# 1_V4.net
KiCad netlist of a schematic drawn in Altium Designer
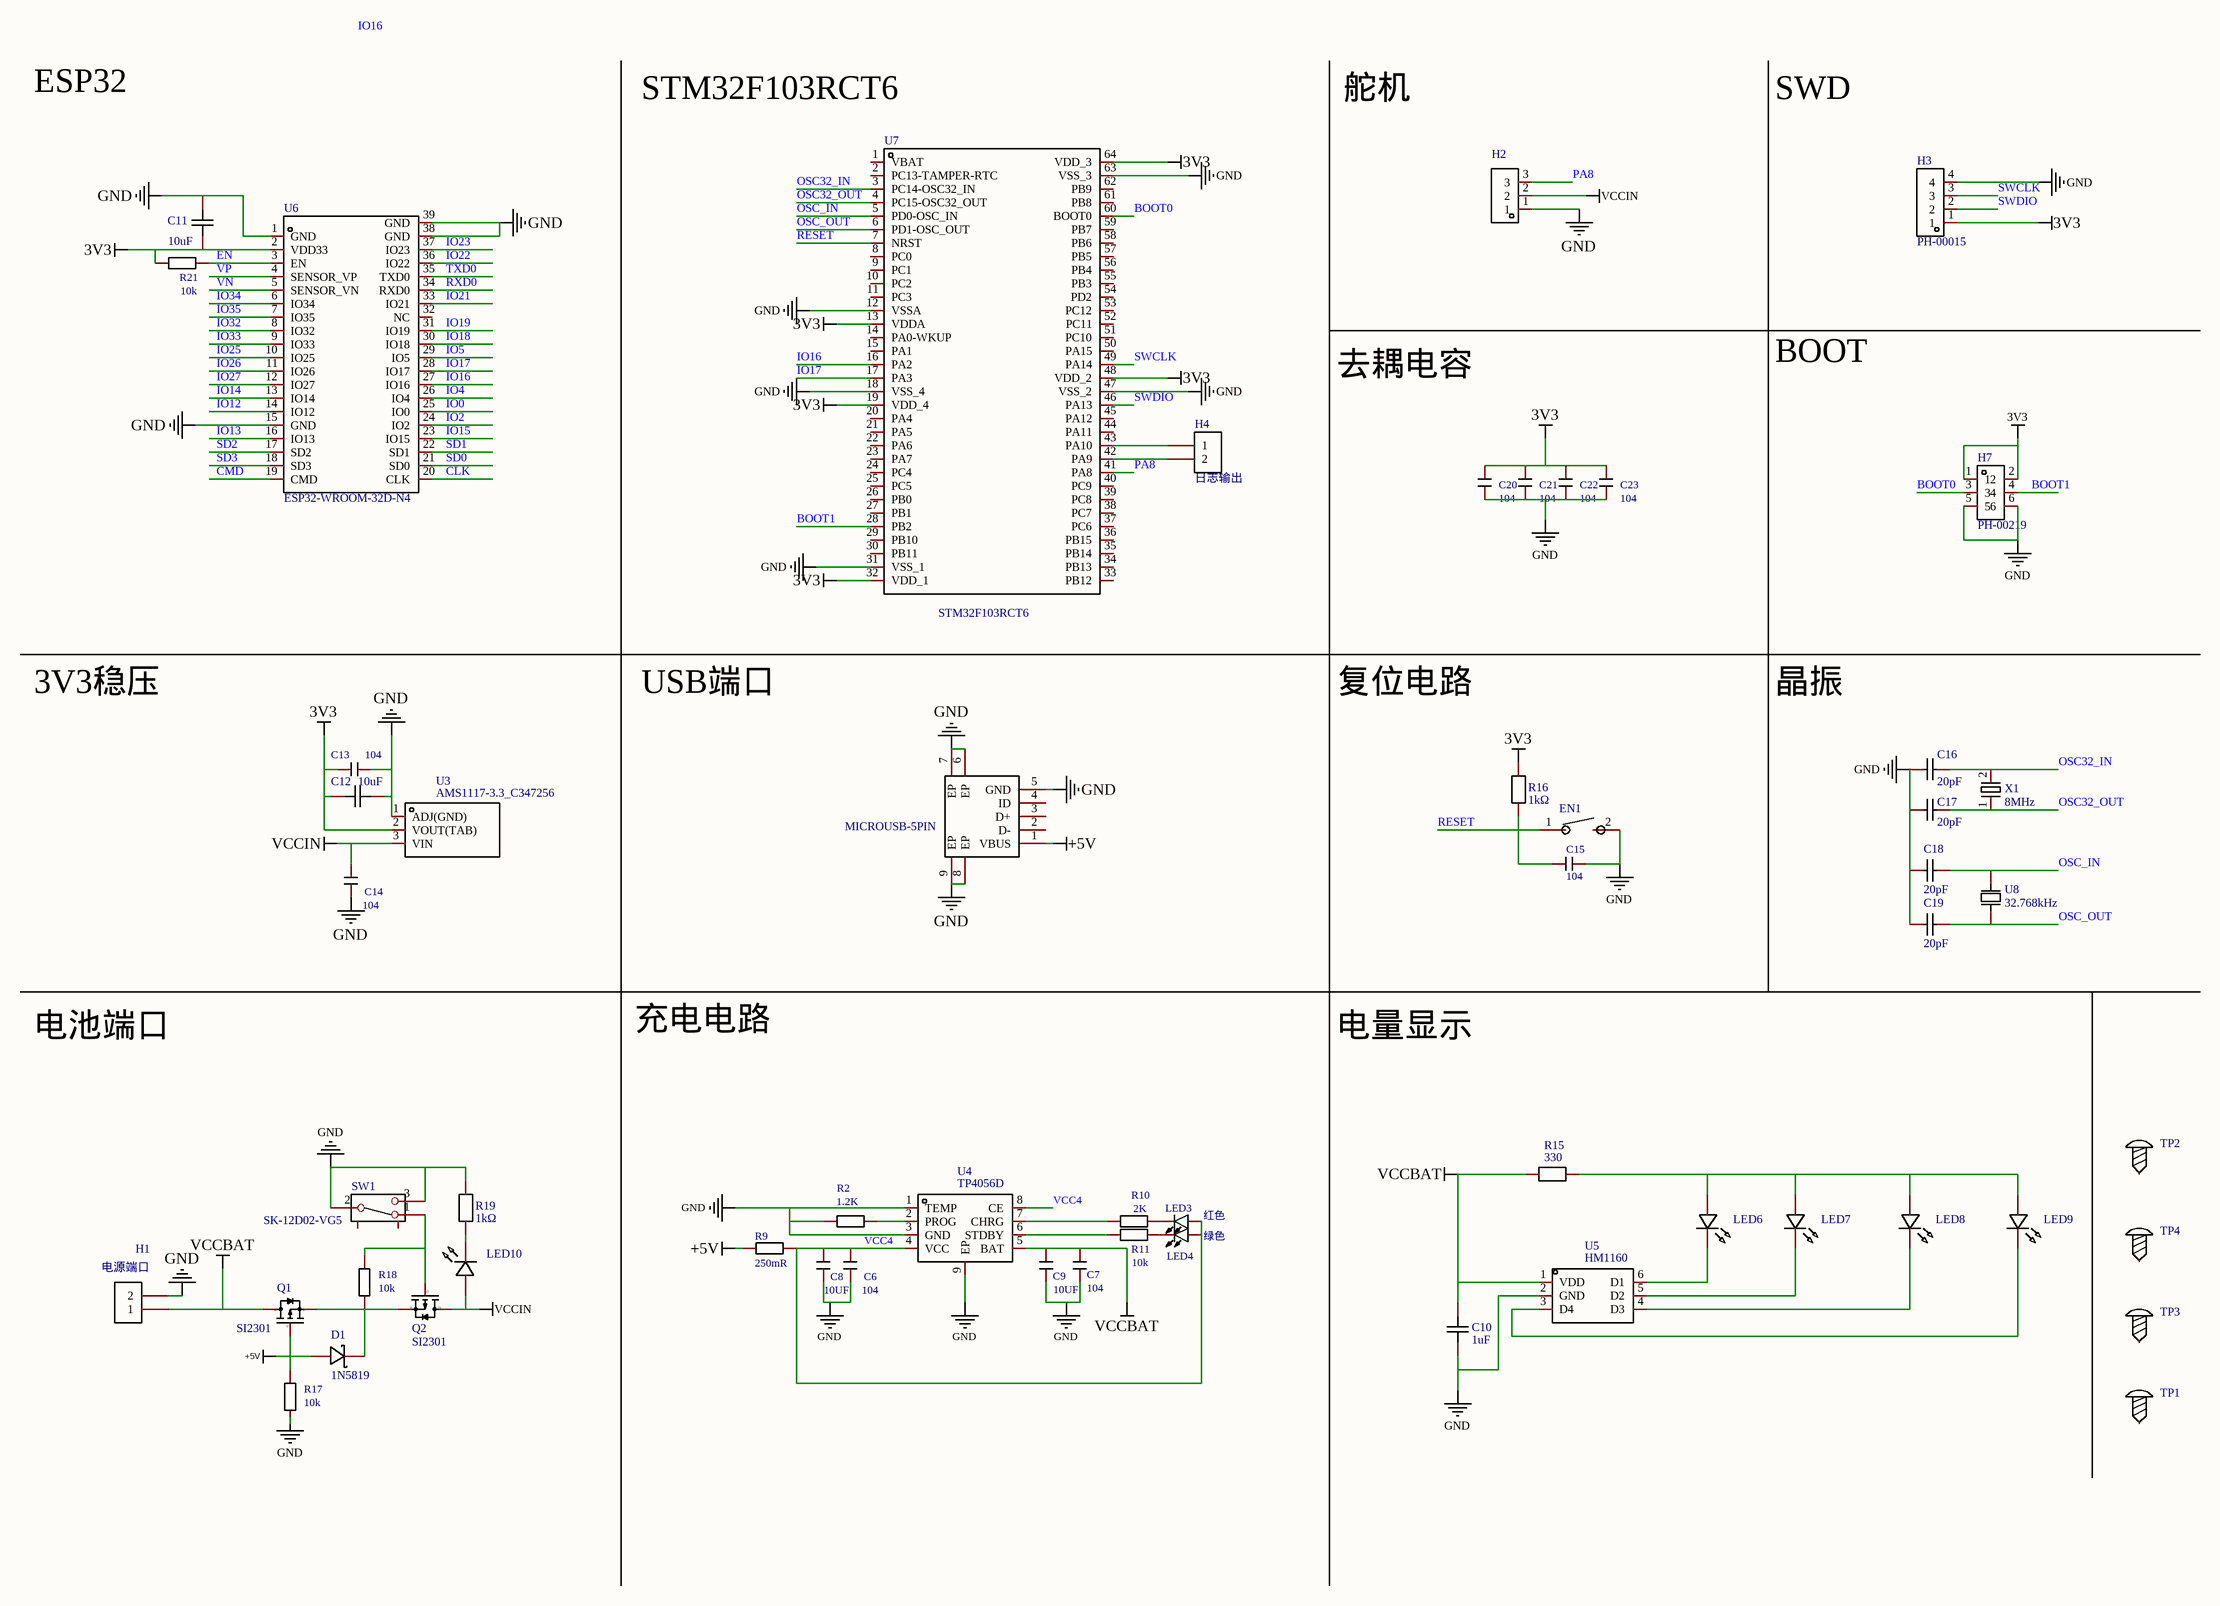
[diagram p0: 1_V4.schdoc]

(export (version "E")
  (design (tool "Eeschema 10.0.6"))
  (components
    (comp (ref "C6")
      (value "104")
      (fields (field (name "NAME") "104") (field (name "版权归属") "源创客"))
      (libsource (lib "altium-import") (part "root_1_104_"))
    )
    (comp (ref "C7")
      (value "104")
      (fields (field (name "NAME") "104") (field (name "版权归属") "源创客"))
      (libsource (lib "altium-import") (part "root_1_104_"))
    )
    (comp (ref "C8")
      (value "10UF")
      (fields (field (name "NAME") "10UF") (field (name "版权归属") "源创客"))
      (libsource (lib "altium-import") (part "root_1_10UF_"))
    )
    (comp (ref "C9")
      (value "10UF")
      (fields (field (name "NAME") "10UF") (field (name "版权归属") "源创客"))
      (libsource (lib "altium-import") (part "root_1_10UF_"))
    )
    (comp (ref "C10")
      (value "1uF")
      (fields (field (name "NAME") "1uF"))
      (libsource (lib "altium-import") (part "root_1_1uF_"))
    )
    (comp (ref "C11")
      (value "10uF")
      (fields (field (name "NAME") "10uF"))
      (libsource (lib "altium-import") (part "root_1_10uF_"))
    )
    (comp (ref "C12")
      (value "10uF")
      (fields (field (name "NAME") "10uF"))
      (libsource (lib "altium-import") (part "root_0_10uF_"))
    )
    (comp (ref "C13")
      (value "104")
      (fields (field (name "NAME") "104") (field (name "版权归属") "源创客"))
      (libsource (lib "altium-import") (part "root_2_104_"))
    )
    (comp (ref "C14")
      (value "104")
      (fields (field (name "NAME") "104") (field (name "版权归属") "源创客"))
      (libsource (lib "altium-import") (part "root_1_104_"))
    )
    (comp (ref "C15")
      (value "104")
      (fields (field (name "NAME") "104") (field (name "版权归属") "源创客"))
      (libsource (lib "altium-import") (part "root_2_104_"))
    )
    (comp (ref "C16")
      (value "20pF")
      (description "温度系数:C0G;容值:20pF;精度:±5%;额定电压:50V;")
      (fields
        (field (name "NAME") "20pF")
        (field (name "MANUFACTURER") "SAMSUNG(三星)")
        (field (name "MANUFACTURER PART") "CL10C200JB8NNNC")
      )
      (libsource (lib "altium-import") (part "root_2_CL10C200JB8NNNC_"))
    )
    (comp (ref "C17")
      (value "20pF")
      (description "温度系数:C0G;容值:20pF;精度:±5%;额定电压:50V;")
      (fields
        (field (name "NAME") "20pF")
        (field (name "MANUFACTURER") "SAMSUNG(三星)")
        (field (name "MANUFACTURER PART") "CL10C200JB8NNNC")
      )
      (libsource (lib "altium-import") (part "root_2_CL10C200JB8NNNC_"))
    )
    (comp (ref "C18")
      (value "20pF")
      (description "温度系数:C0G;容值:20pF;精度:±5%;额定电压:50V;")
      (fields
        (field (name "NAME") "20pF")
        (field (name "MANUFACTURER") "SAMSUNG(三星)")
        (field (name "MANUFACTURER PART") "CL10C200JB8NNNC")
      )
      (libsource (lib "altium-import") (part "root_2_CL10C200JB8NNNC_"))
    )
    (comp (ref "C19")
      (value "20pF")
      (description "温度系数:C0G;容值:20pF;精度:±5%;额定电压:50V;")
      (fields
        (field (name "NAME") "20pF")
        (field (name "MANUFACTURER") "SAMSUNG(三星)")
        (field (name "MANUFACTURER PART") "CL10C200JB8NNNC")
      )
      (libsource (lib "altium-import") (part "root_2_CL10C200JB8NNNC_"))
    )
    (comp (ref "C20")
      (value "104")
      (fields (field (name "NAME") "104") (field (name "版权归属") "源创客"))
      (libsource (lib "altium-import") (part "root_3_104_"))
    )
    (comp (ref "C21")
      (value "104")
      (fields (field (name "NAME") "104") (field (name "版权归属") "源创客"))
      (libsource (lib "altium-import") (part "root_3_104_"))
    )
    (comp (ref "C22")
      (value "104")
      (fields (field (name "NAME") "104") (field (name "版权归属") "源创客"))
      (libsource (lib "altium-import") (part "root_3_104_"))
    )
    (comp (ref "C23")
      (value "104")
      (fields (field (name "NAME") "104") (field (name "版权归属") "源创客"))
      (libsource (lib "altium-import") (part "root_3_104_"))
    )
    (comp (ref "D1")
      (value "1N5819")
      (description "直流反向耐压(Vr):40V;平均整流电流(Io):1A;正向压降(Vf):500mV@1A;")
      (fields (field (name "NAME") "1N5819") (field (name "MANUFACTURER") "KEXIN(科信)"))
      (libsource (lib "altium-import") (part "root_2_1N5819_C437199_"))
    )
    (comp (ref "EN1")
      (value "TSA343G00-250J2")
      (fields (field (name "MANUFACTURER") "BRIGHT(博瑞泰)"))
      (libsource (lib "altium-import") (part "root_0_TSA343G00-250J2_"))
    )
    (comp (ref "H1")
      (value "电源端口")
      (fields
        (field (name "NAME") "电源端口")
        (field (name "MANUFACTURER") "TE Connectivity(美国泰科)")
        (field (name "MANUFACTURER PART") "3-644456-2")
      )
      (libsource (lib "altium-import") (part "root_2_电源端口_"))
    )
    (comp (ref "H2")
      (value "Z-211-0311-0021-001")
      (fields (field (name "MANUFACTURER") "Nextron(正凌)"))
      (libsource (lib "altium-import") (part "root_2_Z-211-0311-0021-001_"))
    )
    (comp (ref "H3")
      (value "PH-00015")
      (fields (field (name "NAME") "PH-00015") (field (name "MANUFACTURER") "Liansheng(连盛)"))
      (libsource (lib "altium-import") (part "root_2_PH-00015_"))
    )
    (comp (ref "H4")
      (value "日志输出")
      (fields
        (field (name "NAME") "日志输出")
        (field (name "MANUFACTURER") "TE Connectivity(美国泰科)")
        (field (name "MANUFACTURER PART") "3-644456-2")
      )
      (libsource (lib "altium-import") (part "root_0_电源端口_"))
    )
    (comp (ref "H7")
      (value "PH-00219")
      (fields (field (name "NAME") "PH-00219") (field (name "MANUFACTURER") "Liansheng(连盛)"))
      (libsource (lib "altium-import") (part "root_0_PH-00219_"))
    )
    (comp (ref "LED3")
      (value "红色")
      (fields (field (name "NAME") "红色") (field (name "版权归属") "源创客"))
      (libsource (lib "altium-import") (part "root_3_红色_"))
    )
    (comp (ref "LED4")
      (value "绿色")
      (fields (field (name "NAME") "绿色") (field (name "版权归属") "源创客"))
      (libsource (lib "altium-import") (part "root_3_绿色_"))
    )
    (comp (ref "LED6")
      (value "LED-0603_R")
      (fields
        (field (name "MANUFACTURER") "EVERLIGHT(台湾亿光)")
        (field (name "MANUFACTURER PART") "19-217/R6C-AL1M2VY/3T")
      )
      (libsource (lib "altium-import") (part "root_3_LED-0603_R_"))
    )
    (comp (ref "LED7")
      (value "LED-0603_R")
      (fields
        (field (name "MANUFACTURER") "EVERLIGHT(台湾亿光)")
        (field (name "MANUFACTURER PART") "19-217/R6C-AL1M2VY/3T")
      )
      (libsource (lib "altium-import") (part "root_3_LED-0603_R_"))
    )
    (comp (ref "LED8")
      (value "LED-0603_R")
      (fields
        (field (name "MANUFACTURER") "EVERLIGHT(台湾亿光)")
        (field (name "MANUFACTURER PART") "19-217/R6C-AL1M2VY/3T")
      )
      (libsource (lib "altium-import") (part "root_3_LED-0603_R_"))
    )
    (comp (ref "LED9")
      (value "LED-0603_R")
      (fields
        (field (name "MANUFACTURER") "EVERLIGHT(台湾亿光)")
        (field (name "MANUFACTURER PART") "19-217/R6C-AL1M2VY/3T")
      )
      (libsource (lib "altium-import") (part "root_3_LED-0603_R_"))
    )
    (comp (ref "LED10")
      (value "LED-0603_R")
      (fields
        (field (name "MANUFACTURER") "EVERLIGHT(台湾亿光)")
        (field (name "MANUFACTURER PART") "19-217/R6C-AL1M2VY/3T")
      )
      (libsource (lib "altium-import") (part "root_1_LED-0603_R_"))
    )
    (comp (ref "NO1")
      (value "MICROUSB-5PIN")
      (fields (field (name "NAME") "MICROUSB-5PIN") (field (name "MANUFACTURER PART") "MicroUSB-5PIN"))
      (libsource (lib "altium-import") (part "root_2_MICROUSB-5PIN_"))
    )
    (comp (ref "Q1")
      (value "SI2301")
      (fields (field (name "NAME") "SI2301") (field (name "MANUFACTURER") "Hottech(合科泰)"))
      (libsource (lib "altium-import") (part "root_1_SI2301_C181086_"))
    )
    (comp (ref "Q2")
      (value "SI2301")
      (fields (field (name "NAME") "SI2301") (field (name "MANUFACTURER") "Hottech(合科泰)"))
      (libsource (lib "altium-import") (part "root_3_SI2301_C181086_"))
    )
    (comp (ref "R2")
      (value "1.2K")
      (fields (field (name "NAME") "1.2K") (field (name "版权归属") "源创客"))
      (libsource (lib "altium-import") (part "root_0_1K_"))
    )
    (comp (ref "R9")
      (value "250mR")
      (fields (field (name "NAME") "250mR") (field (name "版权归属") "源创客"))
      (libsource (lib "altium-import") (part "root_0_250mR_"))
    )
    (comp (ref "R10")
      (value "2K")
      (fields (field (name "NAME") "2K") (field (name "版权归属") "源创客"))
      (libsource (lib "altium-import") (part "root_0_2K_"))
    )
    (comp (ref "R11")
      (value "10k")
      (fields (field (name "NAME") "10k") (field (name "版权归属") "源创客"))
      (libsource (lib "altium-import") (part "root_0_10k_"))
    )
    (comp (ref "R15")
      (value "330")
      (fields (field (name "NAME") "330"))
      (libsource (lib "altium-import") (part "root_0_330_"))
    )
    (comp (ref "R16")
      (value "1kΩ")
      (fields
        (field (name "NAME") "1kΩ")
        (field (name "MANUFACTURER") "PANASONIC(松下)")
        (field (name "MANUFACTURER PART") "ERA3VEB1001V")
        (field (name "TOLERANCE") "±0.1%")
      )
      (libsource (lib "altium-import") (part "root_3_ERA3VEB1001V_"))
    )
    (comp (ref "R17")
      (value "10k")
      (fields (field (name "NAME") "10k") (field (name "版权归属") "源创客"))
      (libsource (lib "altium-import") (part "root_1_10k_"))
    )
    (comp (ref "R18")
      (value "10k")
      (fields (field (name "NAME") "10k") (field (name "版权归属") "源创客"))
      (libsource (lib "altium-import") (part "root_1_10k_"))
    )
    (comp (ref "R19")
      (value "1kΩ")
      (fields
        (field (name "NAME") "1kΩ")
        (field (name "MANUFACTURER") "PANASONIC(松下)")
        (field (name "MANUFACTURER PART") "ERA3VEB1001V")
        (field (name "TOLERANCE") "±0.1%")
      )
      (libsource (lib "altium-import") (part "root_3_ERA3VEB1001V_"))
    )
    (comp (ref "R21")
      (value "10k")
      (fields (field (name "NAME") "10k") (field (name "版权归属") "源创客"))
      (libsource (lib "altium-import") (part "root_0_10k_"))
    )
    (comp (ref "SW1")
      (value "SK-12D02-VG5")
      (fields (field (name "NAME") "SK-12D02-VG5") (field (name "MANUFACTURER") "韩国韩荣"))
      (libsource (lib "altium-import") (part "root_0_SK-12D02-VG5_C136722_"))
    )
    (comp (ref "TP1") (value "M2螺丝") (libsource (lib "altium-import") (part "root_0_M2螺丝_")))
    (comp (ref "TP2") (value "M2螺丝") (libsource (lib "altium-import") (part "root_0_M2螺丝_")))
    (comp (ref "TP3") (value "M2螺丝") (libsource (lib "altium-import") (part "root_0_M2螺丝_")))
    (comp (ref "TP4") (value "M2螺丝") (libsource (lib "altium-import") (part "root_0_M2螺丝_")))
    (comp (ref "U3")
      (value "AMS1117-3.3_C347256")
      (fields
        (field (name "NAME") "AMS1117-3.3_C347256")
        (field (name "MANUFACTURER") "Youtai Semiconductor Co., Ltd.")
        (field (name "MANUFACTURER PART") "AMS1117-3.3")
      )
      (libsource (lib "altium-import") (part "root_0_AMS1117-3.3_C347256_"))
    )
    (comp (ref "U4")
      (value "TP4056D")
      (fields (field (name "NAME") "TP4056D") (field (name "MANUFACTURER") "拓微集成"))
      (libsource (lib "altium-import") (part "root_0_TP4056D_"))
    )
    (comp (ref "U5")
      (value "HM1160")
      (fields
        (field (name "NAME") "HM1160")
        (field (name "MANUFACTURER") "Shenzhen Chip Hope Micro-Electronics")
        (field (name "MANUFACTURER PART") "LP3772-1")
      )
      (libsource (lib "altium-import") (part "root_0_HM1160_"))
    )
    (comp (ref "U6")
      (value "ESP32-WROOM-32D-N4")
      (description "ESP32-WROOM-32D 集成 ESP32-D0WD，功能强大，用途广泛，可以用于低功耗传感器网络和要求极高的任务，例如语音编码、音频流和 MP3 解码等。")
      (fields (field (name "NAME") "ESP32-WROOM-32D-N4") (field (name "MANUFACTURER") "ESPRESSIF(乐鑫)"))
      (libsource (lib "altium-import") (part "root_0_ESP32-WROOM-32D-N4_C473012_"))
    )
    (comp (ref "U7")
      (value "STM32F103RCT6")
      (description "工作电压:2V ~ 3.6V;主频（MAX):72MHz;")
      (fields (field (name "NAME") "STM32F103RCT6") (field (name "MANUFACTURER") "ST(意法半导体)"))
      (libsource (lib "altium-import") (part "root_0_STM32F103RCT6_"))
    )
    (comp (ref "U8")
      (value "32.768kHz")
      (description "晶振类型:贴片无源晶振;频率:32.768kHz;频率公差:±20ppm;负载电容:12.5pF;工作温度:-40℃~+125℃;")
      (fields
        (field (name "NAME") "32.768kHz")
        (field (name "MANUFACTURER") "EPSON(爱普生)")
        (field (name "MANUFACTURER PART") "X1A0000910001")
      )
      (libsource (lib "altium-import") (part "root_1_X1A0000910001_"))
    )
    (comp (ref "X1")
      (value "8MHz")
      (description "晶振类型:49S晶振;频率:8MHz;频率公差:±30ppm;频率稳定度:±50ppm;负载电容:20pF;等效串联电阻(ESR):60Ω;工作温度:-40℃~+85℃;")
      (fields
        (field (name "NAME") "8MHz")
        (field (name "MANUFACTURER") "HCI(杭晶)")
        (field (name "MANUFACTURER PART") "X49ST2-8.000-F20JGDT")
      )
      (libsource (lib "altium-import") (part "root_1_X49ST2-8.000-F20JGDT_"))
    )
  )
  (nets
    (net (code "1") (name "+5V") (class "Default")
      (node (ref "D1") (pin "2") (pinfunction "A_2") (pintype "passive"))
      (node (ref "NO1") (pin "1") (pinfunction "VBUS_1") (pintype "passive"))
      (node (ref "Q1") (pin "1") (pinfunction "G_1") (pintype "passive"))
      (node (ref "R17") (pin "2") (pinfunction "2_2") (pintype "passive"))
      (node (ref "R9") (pin "1") (pinfunction "1_1") (pintype "passive"))
    )
    (net (code "2") (name "/BOOT0") (class "Default")
      (node (ref "H7") (pin "3") (pinfunction "3_3") (pintype "passive"))
      (node (ref "U7") (pin "60") (pinfunction "BOOT0_60") (pintype "passive"))
    )
    (net (code "3") (name "/BOOT1") (class "Default")
      (node (ref "H7") (pin "4") (pinfunction "4_4") (pintype "passive"))
      (node (ref "U7") (pin "28") (pinfunction "PB2_28") (pintype "passive"))
    )
    (net (code "4") (name "/CLK") (class "Default")
      (node (ref "U6") (pin "20") (pinfunction "CLK_20") (pintype "passive"))
    )
    (net (code "5") (name "/CMD") (class "Default")
      (node (ref "U6") (pin "19") (pinfunction "CMD_19") (pintype "passive"))
    )
    (net (code "6") (name "/EN") (class "Default")
      (node (ref "R21") (pin "2") (pinfunction "2_2") (pintype "passive"))
      (node (ref "U6") (pin "3") (pinfunction "EN_3") (pintype "passive"))
    )
    (net (code "7") (name "/IO0") (class "Default")
      (node (ref "U6") (pin "25") (pinfunction "IO0_25") (pintype "passive"))
    )
    (net (code "8") (name "/IO2") (class "Default")
      (node (ref "U6") (pin "24") (pinfunction "IO2_24") (pintype "passive"))
    )
    (net (code "9") (name "/IO4") (class "Default")
      (node (ref "U6") (pin "26") (pinfunction "IO4_26") (pintype "passive"))
    )
    (net (code "10") (name "/IO5") (class "Default")
      (node (ref "U6") (pin "29") (pinfunction "IO5_29") (pintype "passive"))
    )
    (net (code "11") (name "/IO12") (class "Default")
      (node (ref "U6") (pin "14") (pinfunction "IO12_14") (pintype "passive"))
    )
    (net (code "12") (name "/IO13") (class "Default")
      (node (ref "U6") (pin "16") (pinfunction "IO13_16") (pintype "passive"))
    )
    (net (code "13") (name "/IO14") (class "Default")
      (node (ref "U6") (pin "13") (pinfunction "IO14_13") (pintype "passive"))
    )
    (net (code "14") (name "/IO15") (class "Default")
      (node (ref "U6") (pin "23") (pinfunction "IO15_23") (pintype "passive"))
    )
    (net (code "15") (name "/IO16") (class "Default")
      (node (ref "U6") (pin "27") (pinfunction "IO16_27") (pintype "passive"))
      (node (ref "U7") (pin "16") (pinfunction "PA2_16") (pintype "passive"))
    )
    (net (code "16") (name "/IO17") (class "Default")
      (node (ref "U6") (pin "28") (pinfunction "IO17_28") (pintype "passive"))
      (node (ref "U7") (pin "17") (pinfunction "PA3_17") (pintype "passive"))
    )
    (net (code "17") (name "/IO18") (class "Default")
      (node (ref "U6") (pin "30") (pinfunction "IO18_30") (pintype "passive"))
    )
    (net (code "18") (name "/IO19") (class "Default")
      (node (ref "U6") (pin "31") (pinfunction "IO19_31") (pintype "passive"))
    )
    (net (code "19") (name "/IO21") (class "Default")
      (node (ref "U6") (pin "33") (pinfunction "IO21_33") (pintype "passive"))
    )
    (net (code "20") (name "/IO22") (class "Default")
      (node (ref "U6") (pin "36") (pinfunction "IO22_36") (pintype "passive"))
    )
    (net (code "21") (name "/IO23") (class "Default")
      (node (ref "U6") (pin "37") (pinfunction "IO23_37") (pintype "passive"))
    )
    (net (code "22") (name "/IO25") (class "Default")
      (node (ref "U6") (pin "10") (pinfunction "IO25_10") (pintype "passive"))
    )
    (net (code "23") (name "/IO26") (class "Default")
      (node (ref "U6") (pin "11") (pinfunction "IO26_11") (pintype "passive"))
    )
    (net (code "24") (name "/IO27") (class "Default")
      (node (ref "U6") (pin "12") (pinfunction "IO27_12") (pintype "passive"))
    )
    (net (code "25") (name "/IO32") (class "Default")
      (node (ref "U6") (pin "8") (pinfunction "IO32_8") (pintype "passive"))
    )
    (net (code "26") (name "/IO33") (class "Default")
      (node (ref "U6") (pin "9") (pinfunction "IO33_9") (pintype "passive"))
    )
    (net (code "27") (name "/IO34") (class "Default")
      (node (ref "U6") (pin "6") (pinfunction "IO34_6") (pintype "passive"))
    )
    (net (code "28") (name "/IO35") (class "Default")
      (node (ref "U6") (pin "7") (pinfunction "IO35_7") (pintype "passive"))
    )
    (net (code "29") (name "/OSC32_IN") (class "Default")
      (node (ref "C16") (pin "1") (pinfunction "1_1") (pintype "passive"))
      (node (ref "U7") (pin "3") (pinfunction "PC14-OSC32_IN_3") (pintype "passive"))
      (node (ref "X1") (pin "2") (pinfunction "GND_2") (pintype "passive"))
    )
    (net (code "30") (name "/OSC32_OUT") (class "Default")
      (node (ref "C17") (pin "1") (pinfunction "1_1") (pintype "passive"))
      (node (ref "U7") (pin "4") (pinfunction "PC15-OSC32_OUT_4") (pintype "passive"))
      (node (ref "X1") (pin "1") (pinfunction "1_1") (pintype "passive"))
    )
    (net (code "31") (name "/OSC_IN") (class "Default")
      (node (ref "C18") (pin "1") (pinfunction "1_1") (pintype "passive"))
      (node (ref "U7") (pin "5") (pinfunction "PD0-OSC_IN_5") (pintype "passive"))
      (node (ref "U8") (pin "2") (pinfunction "OSC2_2") (pintype "passive"))
    )
    (net (code "32") (name "/OSC_OUT") (class "Default")
      (node (ref "C19") (pin "1") (pinfunction "1_1") (pintype "passive"))
      (node (ref "U7") (pin "6") (pinfunction "PD1-OSC_OUT_6") (pintype "passive"))
      (node (ref "U8") (pin "1") (pinfunction "OSC1_1") (pintype "passive"))
    )
    (net (code "33") (name "/PA8") (class "Default")
      (node (ref "H2") (pin "3") (pinfunction "3_3") (pintype "passive"))
      (node (ref "U7") (pin "41") (pinfunction "PA8_41") (pintype "passive"))
    )
    (net (code "34") (name "/RESET") (class "Default")
      (node (ref "C15") (pin "2") (pinfunction "2_2") (pintype "passive"))
      (node (ref "EN1") (pin "1") (pinfunction "1_1") (pintype "passive"))
      (node (ref "R16") (pin "2") (pinfunction "2_2") (pintype "passive"))
      (node (ref "U7") (pin "7") (pinfunction "NRST_7") (pintype "passive"))
    )
    (net (code "35") (name "/RXD0") (class "Default")
      (node (ref "U6") (pin "34") (pinfunction "RXD0_34") (pintype "passive"))
    )
    (net (code "36") (name "/SD0") (class "Default")
      (node (ref "U6") (pin "21") (pinfunction "SD0_21") (pintype "passive"))
    )
    (net (code "37") (name "/SD1") (class "Default")
      (node (ref "U6") (pin "22") (pinfunction "SD1_22") (pintype "passive"))
    )
    (net (code "38") (name "/SD2") (class "Default")
      (node (ref "U6") (pin "17") (pinfunction "SD2_17") (pintype "passive"))
    )
    (net (code "39") (name "/SD3") (class "Default")
      (node (ref "U6") (pin "18") (pinfunction "SD3_18") (pintype "passive"))
    )
    (net (code "40") (name "/SWCLK") (class "Default")
      (node (ref "H3") (pin "3") (pinfunction "3_3") (pintype "passive"))
      (node (ref "U7") (pin "49") (pinfunction "PA14_49") (pintype "passive"))
    )
    (net (code "41") (name "/SWDIO") (class "Default")
      (node (ref "H3") (pin "2") (pinfunction "2_2") (pintype "passive"))
      (node (ref "U7") (pin "46") (pinfunction "PA13_46") (pintype "passive"))
    )
    (net (code "42") (name "/TXD0") (class "Default")
      (node (ref "U6") (pin "35") (pinfunction "TXD0_35") (pintype "passive"))
    )
    (net (code "43") (name "/VCC4") (class "Default")
      (node (ref "C6") (pin "2") (pinfunction "2_2") (pintype "passive"))
      (node (ref "C8") (pin "2") (pinfunction "2_2") (pintype "passive"))
      (node (ref "LED3") (pin "1") (pinfunction "A_1") (pintype "passive"))
      (node (ref "LED4") (pin "1") (pinfunction "A_1") (pintype "passive"))
      (node (ref "R9") (pin "2") (pinfunction "2_2") (pintype "passive"))
      (node (ref "U4") (pin "4") (pinfunction "VCC_4") (pintype "passive"))
      (node (ref "U4") (pin "8") (pinfunction "CE_8") (pintype "passive"))
    )
    (net (code "44") (name "/VN") (class "Default")
      (node (ref "U6") (pin "5") (pinfunction "SENSOR_VN_5") (pintype "passive"))
    )
    (net (code "45") (name "/VP") (class "Default")
      (node (ref "U6") (pin "4") (pinfunction "SENSOR_VP_4") (pintype "passive"))
    )
    (net (code "46") (name "3V3") (class "Default")
      (node (ref "C11") (pin "1") (pinfunction "1_1") (pintype "passive"))
      (node (ref "C12") (pin "1") (pinfunction "1_1") (pintype "passive"))
      (node (ref "C13") (pin "2") (pinfunction "2_2") (pintype "passive"))
      (node (ref "C20") (pin "1") (pinfunction "1_1") (pintype "passive"))
      (node (ref "C21") (pin "1") (pinfunction "1_1") (pintype "passive"))
      (node (ref "C22") (pin "1") (pinfunction "1_1") (pintype "passive"))
      (node (ref "C23") (pin "1") (pinfunction "1_1") (pintype "passive"))
      (node (ref "H3") (pin "1") (pinfunction "1_1") (pintype "passive"))
      (node (ref "H7") (pin "1") (pinfunction "1_1") (pintype "passive"))
      (node (ref "H7") (pin "2") (pinfunction "2_2") (pintype "passive"))
      (node (ref "R16") (pin "1") (pinfunction "1_1") (pintype "passive"))
      (node (ref "R21") (pin "1") (pinfunction "1_1") (pintype "passive"))
      (node (ref "U3") (pin "2") (pinfunction "VOUT(TAB)_2") (pintype "passive"))
      (node (ref "U6") (pin "2") (pinfunction "VDD33_2") (pintype "passive"))
      (node (ref "U7") (pin "13") (pinfunction "VDDA_13") (pintype "passive"))
      (node (ref "U7") (pin "19") (pinfunction "VDD_4_19") (pintype "passive"))
      (node (ref "U7") (pin "32") (pinfunction "VDD_1_32") (pintype "passive"))
      (node (ref "U7") (pin "48") (pinfunction "VDD_2_48") (pintype "passive"))
      (node (ref "U7") (pin "64") (pinfunction "VDD_3_64") (pintype "passive"))
    )
    (net (code "47") (name "GND") (class "Default")
      (node (ref "C10") (pin "1") (pinfunction "1_1") (pintype "passive"))
      (node (ref "C11") (pin "2") (pinfunction "2_2") (pintype "passive"))
      (node (ref "C12") (pin "2") (pinfunction "2_2") (pintype "passive"))
      (node (ref "C13") (pin "1") (pinfunction "1_1") (pintype "passive"))
      (node (ref "C14") (pin "1") (pinfunction "1_1") (pintype "passive"))
      (node (ref "C15") (pin "1") (pinfunction "1_1") (pintype "passive"))
      (node (ref "C16") (pin "2") (pinfunction "2_2") (pintype "passive"))
      (node (ref "C17") (pin "2") (pinfunction "2_2") (pintype "passive"))
      (node (ref "C18") (pin "2") (pinfunction "2_2") (pintype "passive"))
      (node (ref "C19") (pin "2") (pinfunction "2_2") (pintype "passive"))
      (node (ref "C20") (pin "2") (pinfunction "2_2") (pintype "passive"))
      (node (ref "C21") (pin "2") (pinfunction "2_2") (pintype "passive"))
      (node (ref "C22") (pin "2") (pinfunction "2_2") (pintype "passive"))
      (node (ref "C23") (pin "2") (pinfunction "2_2") (pintype "passive"))
      (node (ref "C6") (pin "1") (pinfunction "1_1") (pintype "passive"))
      (node (ref "C7") (pin "1") (pinfunction "1_1") (pintype "passive"))
      (node (ref "C8") (pin "1") (pinfunction "1_1") (pintype "passive"))
      (node (ref "C9") (pin "1") (pinfunction "1_1") (pintype "passive"))
      (node (ref "EN1") (pin "2") (pinfunction "2_2") (pintype "passive"))
      (node (ref "H1") (pin "2") (pinfunction "2_2") (pintype "passive"))
      (node (ref "H2") (pin "1") (pinfunction "1_1") (pintype "passive"))
      (node (ref "H3") (pin "4") (pinfunction "4_4") (pintype "passive"))
      (node (ref "H7") (pin "5") (pinfunction "5_5") (pintype "passive"))
      (node (ref "H7") (pin "6") (pinfunction "6_6") (pintype "passive"))
      (node (ref "NO1") (pin "5") (pinfunction "GND_5") (pintype "passive"))
      (node (ref "NO1") (pin "6") (pinfunction "EP_6") (pintype "passive"))
      (node (ref "NO1") (pin "7") (pinfunction "EP_7") (pintype "passive"))
      (node (ref "NO1") (pin "8") (pinfunction "EP_8") (pintype "passive"))
      (node (ref "NO1") (pin "9") (pinfunction "EP_9") (pintype "passive"))
      (node (ref "R17") (pin "1") (pinfunction "1_1") (pintype "passive"))
      (node (ref "R19") (pin "1") (pinfunction "1_1") (pintype "passive"))
      (node (ref "R2") (pin "1") (pinfunction "1_1") (pintype "passive"))
      (node (ref "SW1") (pin "2") (pinfunction "2_2") (pintype "passive"))
      (node (ref "SW1") (pin "3") (pinfunction "3_3") (pintype "passive"))
      (node (ref "U3") (pin "1") (pinfunction "ADJ(GND)_1") (pintype "passive"))
      (node (ref "U4") (pin "1") (pinfunction "TEMP_1") (pintype "passive"))
      (node (ref "U4") (pin "3") (pinfunction "GND_3") (pintype "passive"))
      (node (ref "U4") (pin "9") (pinfunction "EP_9") (pintype "passive"))
      (node (ref "U5") (pin "2") (pinfunction "GND_2") (pintype "passive"))
      (node (ref "U6") (pin "1") (pinfunction "GND_1") (pintype "passive"))
      (node (ref "U6") (pin "15") (pinfunction "GND_15") (pintype "passive"))
      (node (ref "U6") (pin "38") (pinfunction "GND_38") (pintype "passive"))
      (node (ref "U6") (pin "39") (pinfunction "GND_39") (pintype "passive"))
      (node (ref "U7") (pin "12") (pinfunction "VSSA_12") (pintype "passive"))
      (node (ref "U7") (pin "18") (pinfunction "VSS_4_18") (pintype "passive"))
      (node (ref "U7") (pin "31") (pinfunction "VSS_1_31") (pintype "passive"))
      (node (ref "U7") (pin "47") (pinfunction "VSS_2_47") (pintype "passive"))
      (node (ref "U7") (pin "63") (pinfunction "VSS_3_63") (pintype "passive"))
    )
    (net (code "48") (name "Net-(D1-C)") (class "Default")
      (node (ref "D1") (pin "1") (pinfunction "C_1") (pintype "passive"))
      (node (ref "Q1") (pin "2") (pinfunction "S_2") (pintype "passive"))
      (node (ref "Q2") (pin "2") (pinfunction "S_2") (pintype "passive"))
      (node (ref "R18") (pin "1") (pinfunction "1_1") (pintype "passive"))
    )
    (net (code "49") (name "Net-(LED3-K)") (class "Default")
      (node (ref "LED3") (pin "2") (pinfunction "K_2") (pintype "passive"))
      (node (ref "R10") (pin "2") (pinfunction "2_2") (pintype "passive"))
    )
    (net (code "50") (name "Net-(LED4-K)") (class "Default")
      (node (ref "LED4") (pin "2") (pinfunction "K_2") (pintype "passive"))
      (node (ref "R11") (pin "2") (pinfunction "2_2") (pintype "passive"))
    )
    (net (code "51") (name "Net-(LED6-Pad1)") (class "Default")
      (node (ref "LED6") (pin "1") (pinfunction "1_1") (pintype "passive"))
      (node (ref "LED7") (pin "1") (pinfunction "1_1") (pintype "passive"))
      (node (ref "LED8") (pin "1") (pinfunction "1_1") (pintype "passive"))
      (node (ref "LED9") (pin "1") (pinfunction "1_1") (pintype "passive"))
      (node (ref "R15") (pin "2") (pinfunction "2_2") (pintype "passive"))
    )
    (net (code "52") (name "Net-(LED10-Pad2)") (class "Default")
      (node (ref "LED10") (pin "2") (pinfunction "2_2") (pintype "passive"))
      (node (ref "R19") (pin "2") (pinfunction "2_2") (pintype "passive"))
    )
    (net (code "53") (name "Net-(Q2-G)") (class "Default")
      (node (ref "Q2") (pin "1") (pinfunction "G_1") (pintype "passive"))
      (node (ref "R18") (pin "2") (pinfunction "2_2") (pintype "passive"))
      (node (ref "SW1") (pin "1") (pinfunction "1_1") (pintype "passive"))
    )
    (net (code "54") (name "Net-(U4-CHRG)") (class "Default")
      (node (ref "R10") (pin "1") (pinfunction "1_1") (pintype "passive"))
      (node (ref "U4") (pin "7") (pinfunction "CHRG_7") (pintype "passive"))
    )
    (net (code "55") (name "Net-(U4-PROG)") (class "Default")
      (node (ref "R2") (pin "2") (pinfunction "2_2") (pintype "passive"))
      (node (ref "U4") (pin "2") (pinfunction "PROG_2") (pintype "passive"))
    )
    (net (code "56") (name "Net-(U4-STDBY)") (class "Default")
      (node (ref "R11") (pin "1") (pinfunction "1_1") (pintype "passive"))
      (node (ref "U4") (pin "6") (pinfunction "STDBY_6") (pintype "passive"))
    )
    (net (code "57") (name "Net-(U5-D1)") (class "Default")
      (node (ref "LED6") (pin "2") (pinfunction "2_2") (pintype "passive"))
      (node (ref "U5") (pin "6") (pinfunction "D1_6") (pintype "passive"))
    )
    (net (code "58") (name "Net-(U5-D2)") (class "Default")
      (node (ref "LED7") (pin "2") (pinfunction "2_2") (pintype "passive"))
      (node (ref "U5") (pin "5") (pinfunction "D2_5") (pintype "passive"))
    )
    (net (code "59") (name "Net-(U5-D3)") (class "Default")
      (node (ref "LED8") (pin "2") (pinfunction "2_2") (pintype "passive"))
      (node (ref "U5") (pin "4") (pinfunction "D3_4") (pintype "passive"))
    )
    (net (code "60") (name "Net-(U5-D4)") (class "Default")
      (node (ref "LED9") (pin "2") (pinfunction "2_2") (pintype "passive"))
      (node (ref "U5") (pin "3") (pinfunction "D4_3") (pintype "passive"))
    )
    (net (code "61") (name "Net-(U7-PA9)") (class "Default")
      (node (ref "H4") (pin "2") (pinfunction "2_2") (pintype "passive"))
      (node (ref "U7") (pin "42") (pinfunction "PA9_42") (pintype "passive"))
    )
    (net (code "62") (name "Net-(U7-PA10)") (class "Default")
      (node (ref "H4") (pin "1") (pinfunction "1_1") (pintype "passive"))
      (node (ref "U7") (pin "43") (pinfunction "PA10_43") (pintype "passive"))
    )
    (net (code "63") (name "VCCBAT") (class "Default")
      (node (ref "C10") (pin "2") (pinfunction "2_2") (pintype "passive"))
      (node (ref "C7") (pin "2") (pinfunction "2_2") (pintype "passive"))
      (node (ref "C9") (pin "2") (pinfunction "2_2") (pintype "passive"))
      (node (ref "H1") (pin "1") (pinfunction "1_1") (pintype "passive"))
      (node (ref "Q1") (pin "3") (pinfunction "D_3") (pintype "passive"))
      (node (ref "R15") (pin "1") (pinfunction "1_1") (pintype "passive"))
      (node (ref "U4") (pin "5") (pinfunction "BAT_5") (pintype "passive"))
      (node (ref "U5") (pin "1") (pinfunction "VDD_1") (pintype "passive"))
    )
    (net (code "64") (name "VCCIN") (class "Default")
      (node (ref "C14") (pin "2") (pinfunction "2_2") (pintype "passive"))
      (node (ref "H2") (pin "2") (pinfunction "2_2") (pintype "passive"))
      (node (ref "LED10") (pin "1") (pinfunction "1_1") (pintype "passive"))
      (node (ref "Q2") (pin "3") (pinfunction "D_3") (pintype "passive"))
      (node (ref "U3") (pin "3") (pinfunction "VIN_3") (pintype "passive"))
    )
    (net (code "65") (name "unconnected-(NO1-D+-Pad3)") (class "Default")
      (node (ref "NO1") (pin "3") (pinfunction "D+_3") (pintype "passive"))
    )
    (net (code "66") (name "unconnected-(NO1-D--Pad2)") (class "Default")
      (node (ref "NO1") (pin "2") (pinfunction "D-_2") (pintype "passive"))
    )
    (net (code "67") (name "unconnected-(NO1-ID-Pad4)") (class "Default")
      (node (ref "NO1") (pin "4") (pinfunction "ID_4") (pintype "passive"))
    )
    (net (code "68") (name "unconnected-(SW1-Pad4)") (class "Default")
      (node (ref "SW1") (pin "4") (pinfunction "4_4") (pintype "passive"))
    )
    (net (code "69") (name "unconnected-(SW1-Pad5)") (class "Default")
      (node (ref "SW1") (pin "5") (pinfunction "5_5") (pintype "passive"))
    )
    (net (code "70") (name "unconnected-(TP1-Pad1)") (class "Default")
      (node (ref "TP1") (pin "1") (pinfunction "1_1") (pintype "passive"))
    )
    (net (code "71") (name "unconnected-(TP2-Pad1)") (class "Default")
      (node (ref "TP2") (pin "1") (pinfunction "1_1") (pintype "passive"))
    )
    (net (code "72") (name "unconnected-(TP3-Pad1)") (class "Default")
      (node (ref "TP3") (pin "1") (pinfunction "1_1") (pintype "passive"))
    )
    (net (code "73") (name "unconnected-(TP4-Pad1)") (class "Default")
      (node (ref "TP4") (pin "1") (pinfunction "1_1") (pintype "passive"))
    )
    (net (code "74") (name "unconnected-(U6-NC-Pad32)") (class "Default")
      (node (ref "U6") (pin "32") (pinfunction "NC_32") (pintype "passive"))
    )
    (net (code "75") (name "unconnected-(U7-PA0-WKUP-Pad14)") (class "Default")
      (node (ref "U7") (pin "14") (pinfunction "PA0-WKUP_14") (pintype "passive"))
    )
    (net (code "76") (name "unconnected-(U7-PA1-Pad15)") (class "Default")
      (node (ref "U7") (pin "15") (pinfunction "PA1_15") (pintype "passive"))
    )
    (net (code "77") (name "unconnected-(U7-PA4-Pad20)") (class "Default")
      (node (ref "U7") (pin "20") (pinfunction "PA4_20") (pintype "passive"))
    )
    (net (code "78") (name "unconnected-(U7-PA5-Pad21)") (class "Default")
      (node (ref "U7") (pin "21") (pinfunction "PA5_21") (pintype "passive"))
    )
    (net (code "79") (name "unconnected-(U7-PA6-Pad22)") (class "Default")
      (node (ref "U7") (pin "22") (pinfunction "PA6_22") (pintype "passive"))
    )
    (net (code "80") (name "unconnected-(U7-PA7-Pad23)") (class "Default")
      (node (ref "U7") (pin "23") (pinfunction "PA7_23") (pintype "passive"))
    )
    (net (code "81") (name "unconnected-(U7-PA11-Pad44)") (class "Default")
      (node (ref "U7") (pin "44") (pinfunction "PA11_44") (pintype "passive"))
    )
    (net (code "82") (name "unconnected-(U7-PA12-Pad45)") (class "Default")
      (node (ref "U7") (pin "45") (pinfunction "PA12_45") (pintype "passive"))
    )
    (net (code "83") (name "unconnected-(U7-PA15-Pad50)") (class "Default")
      (node (ref "U7") (pin "50") (pinfunction "PA15_50") (pintype "passive"))
    )
    (net (code "84") (name "unconnected-(U7-PB0-Pad26)") (class "Default")
      (node (ref "U7") (pin "26") (pinfunction "PB0_26") (pintype "passive"))
    )
    (net (code "85") (name "unconnected-(U7-PB1-Pad27)") (class "Default")
      (node (ref "U7") (pin "27") (pinfunction "PB1_27") (pintype "passive"))
    )
    (net (code "86") (name "unconnected-(U7-PB3-Pad55)") (class "Default")
      (node (ref "U7") (pin "55") (pinfunction "PB3_55") (pintype "passive"))
    )
    (net (code "87") (name "unconnected-(U7-PB4-Pad56)") (class "Default")
      (node (ref "U7") (pin "56") (pinfunction "PB4_56") (pintype "passive"))
    )
    (net (code "88") (name "unconnected-(U7-PB5-Pad57)") (class "Default")
      (node (ref "U7") (pin "57") (pinfunction "PB5_57") (pintype "passive"))
    )
    (net (code "89") (name "unconnected-(U7-PB6-Pad58)") (class "Default")
      (node (ref "U7") (pin "58") (pinfunction "PB6_58") (pintype "passive"))
    )
    (net (code "90") (name "unconnected-(U7-PB7-Pad59)") (class "Default")
      (node (ref "U7") (pin "59") (pinfunction "PB7_59") (pintype "passive"))
    )
    (net (code "91") (name "unconnected-(U7-PB8-Pad61)") (class "Default")
      (node (ref "U7") (pin "61") (pinfunction "PB8_61") (pintype "passive"))
    )
    (net (code "92") (name "unconnected-(U7-PB9-Pad62)") (class "Default")
      (node (ref "U7") (pin "62") (pinfunction "PB9_62") (pintype "passive"))
    )
    (net (code "93") (name "unconnected-(U7-PB10-Pad29)") (class "Default")
      (node (ref "U7") (pin "29") (pinfunction "PB10_29") (pintype "passive"))
    )
    (net (code "94") (name "unconnected-(U7-PB11-Pad30)") (class "Default")
      (node (ref "U7") (pin "30") (pinfunction "PB11_30") (pintype "passive"))
    )
    (net (code "95") (name "unconnected-(U7-PB12-Pad33)") (class "Default")
      (node (ref "U7") (pin "33") (pinfunction "PB12_33") (pintype "passive"))
    )
    (net (code "96") (name "unconnected-(U7-PB13-Pad34)") (class "Default")
      (node (ref "U7") (pin "34") (pinfunction "PB13_34") (pintype "passive"))
    )
    (net (code "97") (name "unconnected-(U7-PB14-Pad35)") (class "Default")
      (node (ref "U7") (pin "35") (pinfunction "PB14_35") (pintype "passive"))
    )
    (net (code "98") (name "unconnected-(U7-PB15-Pad36)") (class "Default")
      (node (ref "U7") (pin "36") (pinfunction "PB15_36") (pintype "passive"))
    )
    (net (code "99") (name "unconnected-(U7-PC0-Pad8)") (class "Default")
      (node (ref "U7") (pin "8") (pinfunction "PC0_8") (pintype "passive"))
    )
    (net (code "100") (name "unconnected-(U7-PC1-Pad9)") (class "Default")
      (node (ref "U7") (pin "9") (pinfunction "PC1_9") (pintype "passive"))
    )
    (net (code "101") (name "unconnected-(U7-PC2-Pad10)") (class "Default")
      (node (ref "U7") (pin "10") (pinfunction "PC2_10") (pintype "passive"))
    )
    (net (code "102") (name "unconnected-(U7-PC3-Pad11)") (class "Default")
      (node (ref "U7") (pin "11") (pinfunction "PC3_11") (pintype "passive"))
    )
    (net (code "103") (name "unconnected-(U7-PC4-Pad24)") (class "Default")
      (node (ref "U7") (pin "24") (pinfunction "PC4_24") (pintype "passive"))
    )
    (net (code "104") (name "unconnected-(U7-PC5-Pad25)") (class "Default")
      (node (ref "U7") (pin "25") (pinfunction "PC5_25") (pintype "passive"))
    )
    (net (code "105") (name "unconnected-(U7-PC6-Pad37)") (class "Default")
      (node (ref "U7") (pin "37") (pinfunction "PC6_37") (pintype "passive"))
    )
    (net (code "106") (name "unconnected-(U7-PC7-Pad38)") (class "Default")
      (node (ref "U7") (pin "38") (pinfunction "PC7_38") (pintype "passive"))
    )
    (net (code "107") (name "unconnected-(U7-PC8-Pad39)") (class "Default")
      (node (ref "U7") (pin "39") (pinfunction "PC8_39") (pintype "passive"))
    )
    (net (code "108") (name "unconnected-(U7-PC9-Pad40)") (class "Default")
      (node (ref "U7") (pin "40") (pinfunction "PC9_40") (pintype "passive"))
    )
    (net (code "109") (name "unconnected-(U7-PC10-Pad51)") (class "Default")
      (node (ref "U7") (pin "51") (pinfunction "PC10_51") (pintype "passive"))
    )
    (net (code "110") (name "unconnected-(U7-PC11-Pad52)") (class "Default")
      (node (ref "U7") (pin "52") (pinfunction "PC11_52") (pintype "passive"))
    )
    (net (code "111") (name "unconnected-(U7-PC12-Pad53)") (class "Default")
      (node (ref "U7") (pin "53") (pinfunction "PC12_53") (pintype "passive"))
    )
    (net (code "112") (name "unconnected-(U7-PC13-TAMPER-RTC-Pad2)") (class "Default")
      (node (ref "U7") (pin "2") (pinfunction "PC13-TAMPER-RTC_2") (pintype "passive"))
    )
    (net (code "113") (name "unconnected-(U7-PD2-Pad54)") (class "Default")
      (node (ref "U7") (pin "54") (pinfunction "PD2_54") (pintype "passive"))
    )
    (net (code "114") (name "unconnected-(U7-VBAT-Pad1)") (class "Default")
      (node (ref "U7") (pin "1") (pinfunction "VBAT_1") (pintype "passive"))
    )
  )
)
